# squall-blees-board.net
KiCad netlist of a schematic drawn in EAGLE
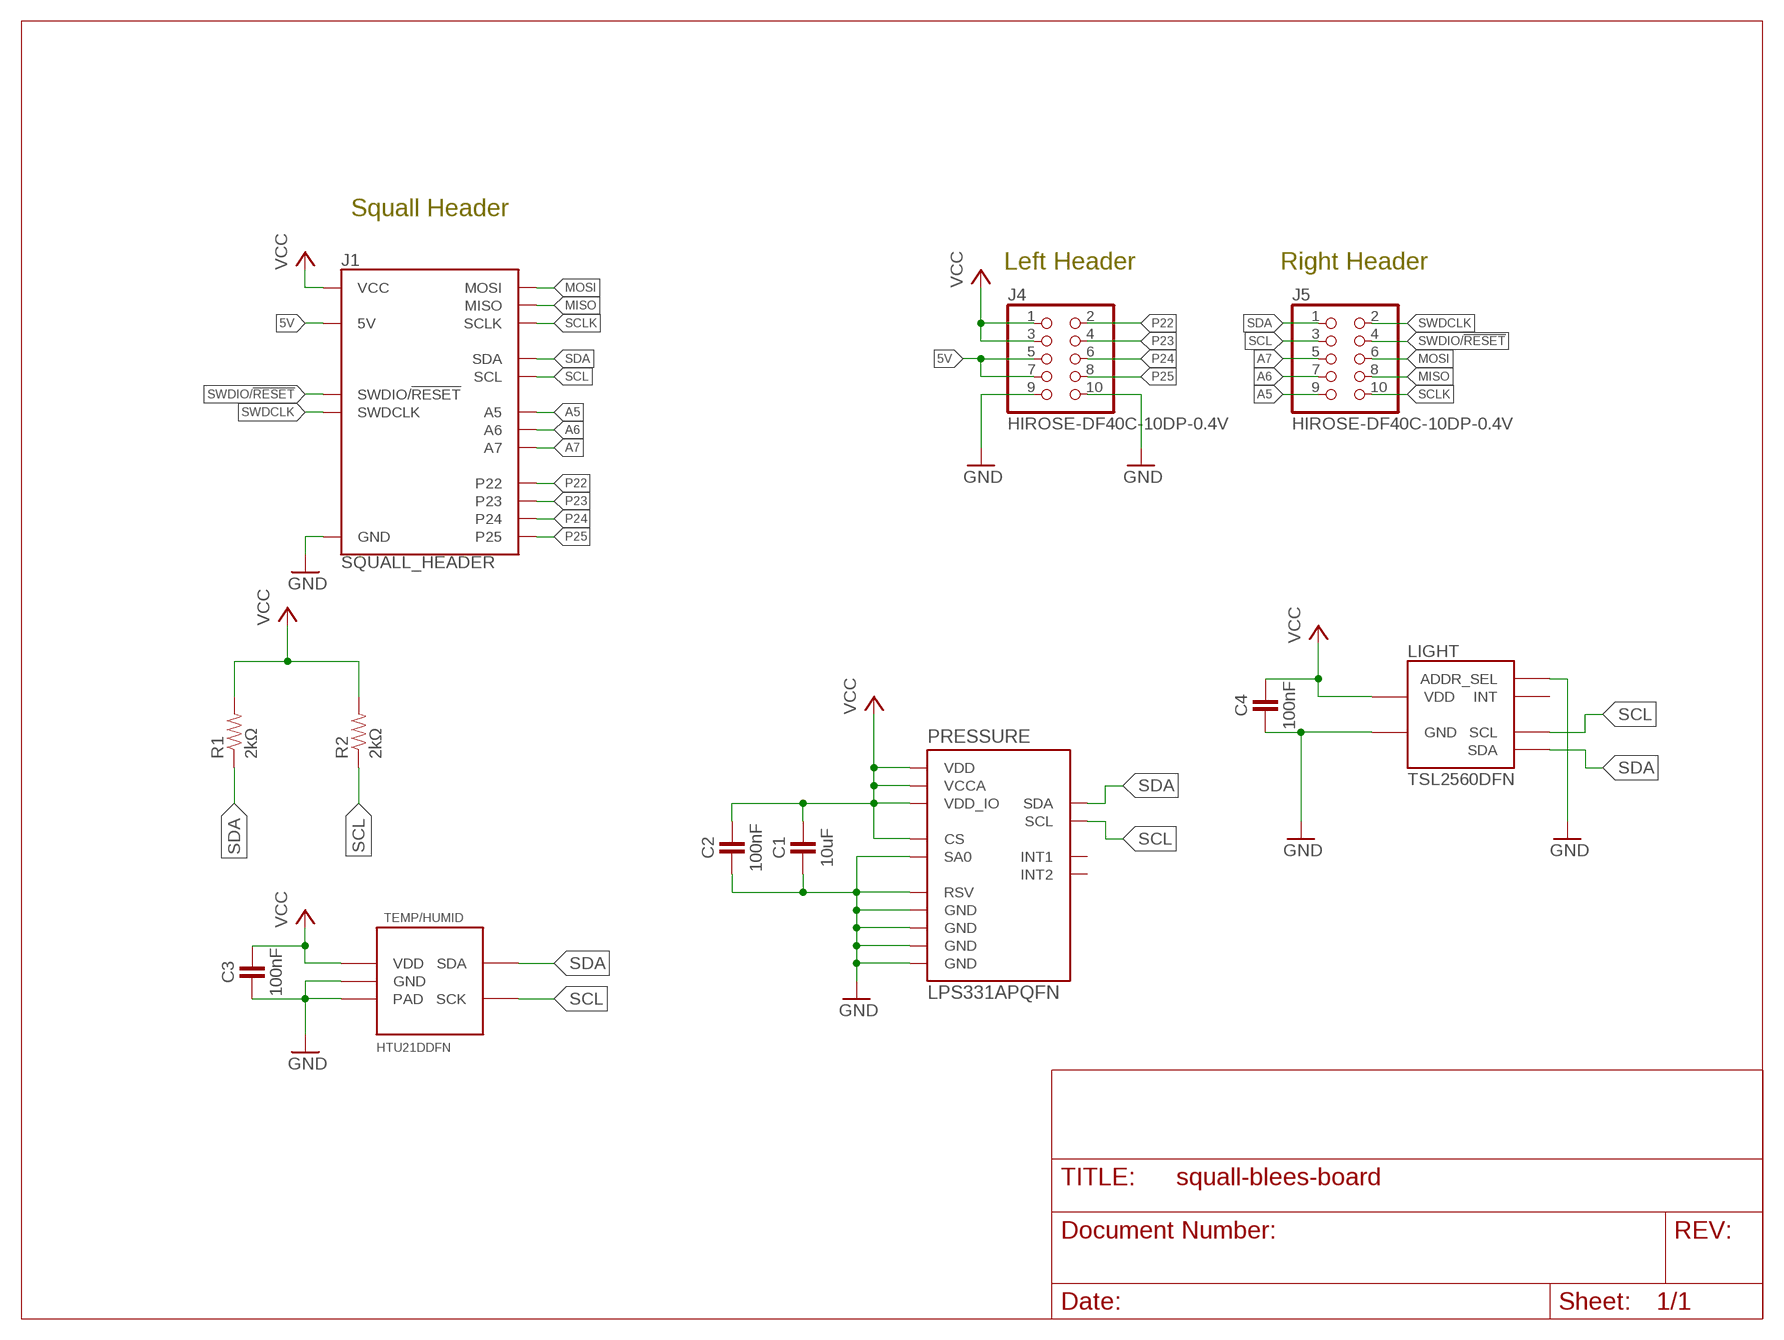
[diagram p0: schematic, sheet 1]

(export (version "E")
  (design (tool "Eeschema 10.0.6"))
  (components
    (comp (ref "C1")
      (value "10uF")
      (footprint "eagle-import:0603_CAP")
      (libsource (lib "eagle-import") (part "CAPACITOR0603_CAP"))
    )
    (comp (ref "C2")
      (value "100nF")
      (footprint "eagle-import:0402_CAP")
      (libsource (lib "eagle-import") (part "CAPACITOR"))
    )
    (comp (ref "C3")
      (value "100nF")
      (footprint "eagle-import:0402_CAP")
      (libsource (lib "eagle-import") (part "CAPACITOR"))
    )
    (comp (ref "C4")
      (value "100nF")
      (footprint "eagle-import:0402_CAP")
      (libsource (lib "eagle-import") (part "CAPACITOR"))
    )
    (comp (ref "J1")
      (value "SQUALL_HEADER")
      (footprint "eagle-import:SQUALL_HEADER")
      (libsource (lib "eagle-import") (part "SQUALL_HEADER"))
    )
    (comp (ref "J4")
      (value "HIROSE-DF40C-10DP-0.4V")
      (footprint "eagle-import:2X5_SMD_0.4MM")
      (libsource (lib "eagle-import") (part "HIROSE-DF40C-10DP-0.4V"))
    )
    (comp (ref "J5")
      (value "HIROSE-DF40C-10DP-0.4V")
      (footprint "eagle-import:2X5_SMD_0.4MM")
      (libsource (lib "eagle-import") (part "HIROSE-DF40C-10DP-0.4V"))
    )
    (comp (ref "LIGHT")
      (value "TSL2560DFN")
      (footprint "eagle-import:DFN2")
      (libsource (lib "eagle-import") (part "TSL2560DFN"))
    )
    (comp (ref "PRESSURE")
      (value "LPS331APQFN")
      (footprint "eagle-import:HCLGA-16L")
      (libsource (lib "eagle-import") (part "LPS331APQFN"))
    )
    (comp (ref "R1")
      (value "2kΩ")
      (footprint "eagle-import:0402_RES")
      (libsource (lib "eagle-import") (part "RESISTOR0402_RES"))
    )
    (comp (ref "R2")
      (value "2kΩ")
      (footprint "eagle-import:0402_RES")
      (libsource (lib "eagle-import") (part "RESISTOR0402_RES"))
    )
    (comp (ref "TEMP/HUMID")
      (value "HTU21DDFN")
      (footprint "eagle-import:DFN")
      (libsource (lib "eagle-import") (part "HTU21DDFN"))
    )
  )
  (nets
    (net (code "1") (name "/SWDIO{slash}~{RESET}") (class "Default")
      (node (ref "J1") (pin "B4") (pinfunction "SWDIO/~{RESET}_B4") (pintype "bidirectional"))
      (node (ref "J5") (pin "4") (pinfunction "4_4") (pintype "passive"))
    )
    (net (code "2") (name "5V") (class "Default")
      (node (ref "J1") (pin "A5") (pinfunction "5V_A5") (pintype "bidirectional"))
      (node (ref "J1") (pin "A7") (pinfunction "5V_A7") (pintype "bidirectional"))
      (node (ref "J4") (pin "5") (pinfunction "5_5") (pintype "passive"))
      (node (ref "J4") (pin "7") (pinfunction "7_7") (pintype "passive"))
    )
    (net (code "3") (name "A5") (class "Default")
      (node (ref "J1") (pin "B9") (pinfunction "A5_B9") (pintype "bidirectional"))
      (node (ref "J5") (pin "9") (pinfunction "9_9") (pintype "passive"))
    )
    (net (code "4") (name "A6") (class "Default")
      (node (ref "J1") (pin "B7") (pinfunction "A6_B7") (pintype "bidirectional"))
      (node (ref "J5") (pin "7") (pinfunction "7_7") (pintype "passive"))
    )
    (net (code "5") (name "A7") (class "Default")
      (node (ref "J1") (pin "B5") (pinfunction "A7_B5") (pintype "bidirectional"))
      (node (ref "J5") (pin "5") (pinfunction "5_5") (pintype "passive"))
    )
    (net (code "6") (name "GND") (class "Default")
      (node (ref "C1") (pin "2") (pinfunction "2_2") (pintype "bidirectional"))
      (node (ref "C2") (pin "2") (pinfunction "2_2") (pintype "bidirectional"))
      (node (ref "C3") (pin "2") (pinfunction "2_2") (pintype "bidirectional"))
      (node (ref "C4") (pin "2") (pinfunction "2_2") (pintype "bidirectional"))
      (node (ref "J1") (pin "A10") (pinfunction "GND_A10") (pintype "bidirectional"))
      (node (ref "J1") (pin "A9") (pinfunction "GND_A9") (pintype "bidirectional"))
      (node (ref "J4") (pin "10") (pinfunction "10_10") (pintype "passive"))
      (node (ref "J4") (pin "9") (pinfunction "9_9") (pintype "passive"))
      (node (ref "LIGHT") (pin "2") (pinfunction "ADDR_SEL_2") (pintype "bidirectional"))
      (node (ref "LIGHT") (pin "3") (pinfunction "GND_3") (pintype "power_in"))
      (node (ref "PRESSURE") (pin "10") (pinfunction "RSV_10") (pintype "power_in"))
      (node (ref "PRESSURE") (pin "12") (pinfunction "GND_12") (pintype "power_in"))
      (node (ref "PRESSURE") (pin "13") (pinfunction "GND_13") (pintype "power_in"))
      (node (ref "PRESSURE") (pin "16") (pinfunction "GND_16") (pintype "power_in"))
      (node (ref "PRESSURE") (pin "5") (pinfunction "GND_5") (pintype "power_in"))
      (node (ref "PRESSURE") (pin "7") (pinfunction "SA0_7") (pintype "input"))
      (node (ref "TEMP/HUMID") (pin "2") (pinfunction "GND_2") (pintype "power_in"))
      (node (ref "TEMP/HUMID") (pin "PAD") (pinfunction "PAD_PAD") (pintype "power_in"))
    )
    (net (code "7") (name "MISO") (class "Default")
      (node (ref "J1") (pin "B8") (pinfunction "MISO_B8") (pintype "bidirectional"))
      (node (ref "J5") (pin "8") (pinfunction "8_8") (pintype "passive"))
    )
    (net (code "8") (name "MOSI") (class "Default")
      (node (ref "J1") (pin "B6") (pinfunction "MOSI_B6") (pintype "bidirectional"))
      (node (ref "J5") (pin "6") (pinfunction "6_6") (pintype "passive"))
    )
    (net (code "9") (name "P22") (class "Default")
      (node (ref "J1") (pin "A2") (pinfunction "P22_A2") (pintype "bidirectional"))
      (node (ref "J4") (pin "2") (pinfunction "2_2") (pintype "passive"))
    )
    (net (code "10") (name "P23") (class "Default")
      (node (ref "J1") (pin "A4") (pinfunction "P23_A4") (pintype "bidirectional"))
      (node (ref "J4") (pin "4") (pinfunction "4_4") (pintype "passive"))
    )
    (net (code "11") (name "P24") (class "Default")
      (node (ref "J1") (pin "A6") (pinfunction "P24_A6") (pintype "bidirectional"))
      (node (ref "J4") (pin "6") (pinfunction "6_6") (pintype "passive"))
    )
    (net (code "12") (name "P25") (class "Default")
      (node (ref "J1") (pin "A8") (pinfunction "P25_A8") (pintype "bidirectional"))
      (node (ref "J4") (pin "8") (pinfunction "8_8") (pintype "passive"))
    )
    (net (code "13") (name "SCL") (class "Default")
      (node (ref "J1") (pin "B3") (pinfunction "SCL_B3") (pintype "bidirectional"))
      (node (ref "J5") (pin "3") (pinfunction "3_3") (pintype "passive"))
      (node (ref "LIGHT") (pin "4") (pinfunction "SCL_4") (pintype "bidirectional"))
      (node (ref "PRESSURE") (pin "4") (pinfunction "SCL_4") (pintype "bidirectional"))
      (node (ref "R2") (pin "1") (pinfunction "1_1") (pintype "passive"))
      (node (ref "TEMP/HUMID") (pin "6") (pinfunction "SCK_6") (pintype "bidirectional"))
    )
    (net (code "14") (name "SCLK") (class "Default")
      (node (ref "J1") (pin "B10") (pinfunction "SCLK_B10") (pintype "bidirectional"))
      (node (ref "J5") (pin "10") (pinfunction "10_10") (pintype "passive"))
    )
    (net (code "15") (name "SDA") (class "Default")
      (node (ref "J1") (pin "B1") (pinfunction "SDA_B1") (pintype "bidirectional"))
      (node (ref "J5") (pin "1") (pinfunction "1_1") (pintype "passive"))
      (node (ref "LIGHT") (pin "6") (pinfunction "SDA_6") (pintype "bidirectional"))
      (node (ref "PRESSURE") (pin "6") (pinfunction "SDA_6") (pintype "bidirectional"))
      (node (ref "R1") (pin "1") (pinfunction "1_1") (pintype "passive"))
      (node (ref "TEMP/HUMID") (pin "1") (pinfunction "SDA_1") (pintype "bidirectional"))
    )
    (net (code "16") (name "SWDCLK") (class "Default")
      (node (ref "J1") (pin "B2") (pinfunction "SWDCLK_B2") (pintype "bidirectional"))
      (node (ref "J5") (pin "2") (pinfunction "2_2") (pintype "passive"))
    )
    (net (code "17") (name "VCC") (class "Default")
      (node (ref "C1") (pin "1") (pinfunction "1_1") (pintype "bidirectional"))
      (node (ref "C2") (pin "1") (pinfunction "1_1") (pintype "bidirectional"))
      (node (ref "C3") (pin "1") (pinfunction "1_1") (pintype "bidirectional"))
      (node (ref "C4") (pin "1") (pinfunction "1_1") (pintype "bidirectional"))
      (node (ref "J1") (pin "A1") (pinfunction "VCC_A1") (pintype "bidirectional"))
      (node (ref "J1") (pin "A3") (pinfunction "VCC_A3") (pintype "bidirectional"))
      (node (ref "J4") (pin "1") (pinfunction "1_1") (pintype "passive"))
      (node (ref "J4") (pin "3") (pinfunction "3_3") (pintype "passive"))
      (node (ref "LIGHT") (pin "1") (pinfunction "VDD_1") (pintype "power_in"))
      (node (ref "PRESSURE") (pin "1") (pinfunction "VDD_IO_1") (pintype "power_in"))
      (node (ref "PRESSURE") (pin "14") (pinfunction "VDD_14") (pintype "power_in"))
      (node (ref "PRESSURE") (pin "15") (pinfunction "VCCA_15") (pintype "power_in"))
      (node (ref "PRESSURE") (pin "8") (pinfunction "CS_8") (pintype "input"))
      (node (ref "R1") (pin "2") (pinfunction "2_2") (pintype "passive"))
      (node (ref "R2") (pin "2") (pinfunction "2_2") (pintype "passive"))
      (node (ref "TEMP/HUMID") (pin "5") (pinfunction "VDD_5") (pintype "power_in"))
    )
    (net (code "18") (name "unconnected-(LIGHT-INT-Pad5)") (class "Default")
      (node (ref "LIGHT") (pin "5") (pinfunction "INT_5") (pintype "bidirectional"))
    )
    (net (code "19") (name "unconnected-(PRESSURE-INT1-Pad11)") (class "Default")
      (node (ref "PRESSURE") (pin "11") (pinfunction "INT1_11") (pintype "bidirectional"))
    )
    (net (code "20") (name "unconnected-(PRESSURE-INT2-Pad9)") (class "Default")
      (node (ref "PRESSURE") (pin "9") (pinfunction "INT2_9") (pintype "bidirectional"))
    )
  )
)
